# M113B.net
KiCad netlist of a schematic drawn in EAGLE
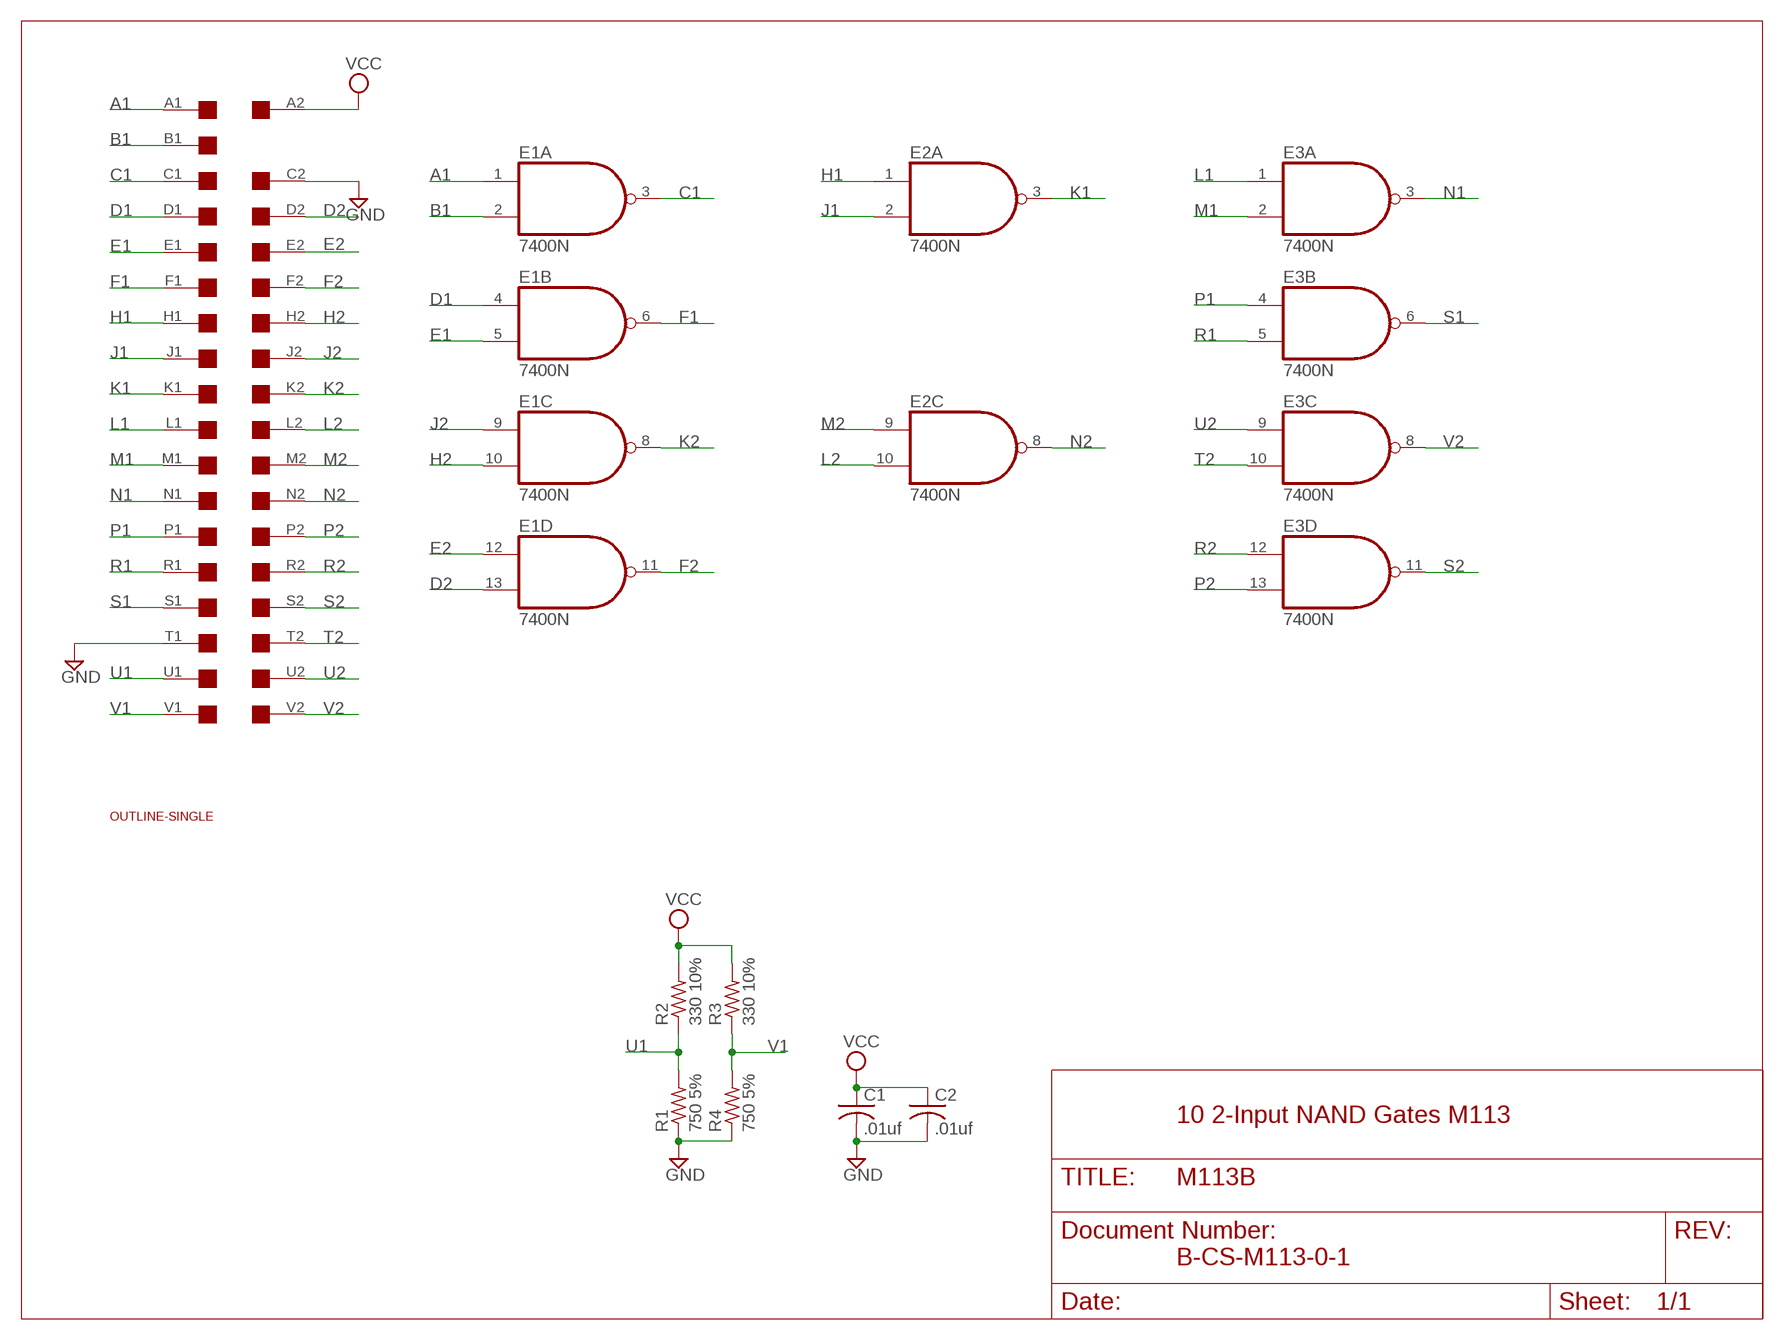
[diagram p0: schematic, sheet 1]

(export (version "E")
  (design (tool "Eeschema 10.0.6"))
  (components
    (comp (ref "C1")
      (value ".01uf")
      (footprint "eagle-import:C075-032X103")
      (libsource (lib "eagle-import") (part "C-US075-032X103"))
    )
    (comp (ref "C2")
      (value ".01uf")
      (footprint "eagle-import:C075-032X103")
      (libsource (lib "eagle-import") (part "C-US075-032X103"))
    )
    (comp (ref "E1")
      (value "7400N")
      (footprint "eagle-import:DIL14")
      (libsource (lib "eagle-import") (part "7400N"))
    )
    (comp (ref "E2")
      (value "7400N")
      (footprint "eagle-import:DIL14")
      (libsource (lib "eagle-import") (part "7400N"))
    )
    (comp (ref "E3")
      (value "7400N")
      (footprint "eagle-import:DIL14")
      (libsource (lib "eagle-import") (part "7400N"))
    )
    (comp (ref "R1")
      (value "750 5%")
      (footprint "eagle-import:0207_15")
      (libsource (lib "eagle-import") (part "R-US_0207/15"))
    )
    (comp (ref "R2")
      (value "330 10%")
      (footprint "eagle-import:0207_15")
      (libsource (lib "eagle-import") (part "R-US_0207/15"))
    )
    (comp (ref "R3")
      (value "330 10%")
      (footprint "eagle-import:0207_15")
      (libsource (lib "eagle-import") (part "R-US_0207/15"))
    )
    (comp (ref "R4")
      (value "750 5%")
      (footprint "eagle-import:0207_15")
      (libsource (lib "eagle-import") (part "R-US_0207/15"))
    )
    (comp (ref "U$1")
      (value "SINGLE")
      (footprint "eagle-import:EDGE-CON2")
      (libsource (lib "eagle-import") (part "SINGLE"))
    )
    (comp (ref "U$4")
      (value "OUTLINE-SINGLE")
      (footprint "eagle-import:SINGLE")
      (libsource (lib "eagle-import") (part "OUTLINE-SINGLE"))
    )
  )
  (nets
    (net (code "1") (name "/A1") (class "Default")
      (node (ref "E1") (pin "1") (pinfunction "I0_1") (pintype "input"))
      (node (ref "U$1") (pin "A1") (pinfunction "1_A1") (pintype "bidirectional"))
    )
    (net (code "2") (name "/B1") (class "Default")
      (node (ref "E1") (pin "2") (pinfunction "I1_2") (pintype "input"))
      (node (ref "U$1") (pin "B1") (pinfunction "1_B1") (pintype "bidirectional"))
    )
    (net (code "3") (name "/C1") (class "Default")
      (node (ref "E1") (pin "3") (pinfunction "O_3") (pintype "output"))
      (node (ref "U$1") (pin "C1") (pinfunction "1_C1") (pintype "bidirectional"))
    )
    (net (code "4") (name "/D1") (class "Default")
      (node (ref "E1") (pin "4") (pinfunction "I0_4") (pintype "input"))
      (node (ref "U$1") (pin "D1") (pinfunction "1_D1") (pintype "bidirectional"))
    )
    (net (code "5") (name "/D2") (class "Default")
      (node (ref "E1") (pin "13") (pinfunction "I1_13") (pintype "input"))
      (node (ref "U$1") (pin "D2") (pinfunction "1_D2") (pintype "bidirectional"))
    )
    (net (code "6") (name "/E1") (class "Default")
      (node (ref "E1") (pin "5") (pinfunction "I1_5") (pintype "input"))
      (node (ref "U$1") (pin "E1") (pinfunction "1_E1") (pintype "bidirectional"))
    )
    (net (code "7") (name "/E2") (class "Default")
      (node (ref "E1") (pin "12") (pinfunction "I0_12") (pintype "input"))
      (node (ref "U$1") (pin "E2") (pinfunction "1_E2") (pintype "bidirectional"))
    )
    (net (code "8") (name "/F1") (class "Default")
      (node (ref "E1") (pin "6") (pinfunction "O_6") (pintype "output"))
      (node (ref "U$1") (pin "F1") (pinfunction "1_F1") (pintype "bidirectional"))
    )
    (net (code "9") (name "/F2") (class "Default")
      (node (ref "E1") (pin "11") (pinfunction "O_11") (pintype "output"))
      (node (ref "U$1") (pin "F2") (pinfunction "1_F2") (pintype "bidirectional"))
    )
    (net (code "10") (name "/H1") (class "Default")
      (node (ref "E2") (pin "1") (pinfunction "I0_1") (pintype "input"))
      (node (ref "U$1") (pin "H1") (pinfunction "1_H1") (pintype "bidirectional"))
    )
    (net (code "11") (name "/H2") (class "Default")
      (node (ref "E1") (pin "10") (pinfunction "I1_10") (pintype "input"))
      (node (ref "U$1") (pin "H2") (pinfunction "1_H2") (pintype "bidirectional"))
    )
    (net (code "12") (name "/J1") (class "Default")
      (node (ref "E2") (pin "2") (pinfunction "I1_2") (pintype "input"))
      (node (ref "U$1") (pin "J1") (pinfunction "1_J1") (pintype "bidirectional"))
    )
    (net (code "13") (name "/J2") (class "Default")
      (node (ref "E1") (pin "9") (pinfunction "I0_9") (pintype "input"))
      (node (ref "U$1") (pin "J2") (pinfunction "1_J2") (pintype "bidirectional"))
    )
    (net (code "14") (name "/K1") (class "Default")
      (node (ref "E2") (pin "3") (pinfunction "O_3") (pintype "output"))
      (node (ref "U$1") (pin "K1") (pinfunction "1_K1") (pintype "bidirectional"))
    )
    (net (code "15") (name "/K2") (class "Default")
      (node (ref "E1") (pin "8") (pinfunction "O_8") (pintype "output"))
      (node (ref "U$1") (pin "K2") (pinfunction "1_K2") (pintype "bidirectional"))
    )
    (net (code "16") (name "/L1") (class "Default")
      (node (ref "E3") (pin "1") (pinfunction "I0_1") (pintype "input"))
      (node (ref "U$1") (pin "L1") (pinfunction "1_L1") (pintype "bidirectional"))
    )
    (net (code "17") (name "/L2") (class "Default")
      (node (ref "E2") (pin "10") (pinfunction "I1_10") (pintype "input"))
      (node (ref "U$1") (pin "L2") (pinfunction "1_L2") (pintype "bidirectional"))
    )
    (net (code "18") (name "/M1") (class "Default")
      (node (ref "E3") (pin "2") (pinfunction "I1_2") (pintype "input"))
      (node (ref "U$1") (pin "M1") (pinfunction "1_M1") (pintype "bidirectional"))
    )
    (net (code "19") (name "/M2") (class "Default")
      (node (ref "E2") (pin "9") (pinfunction "I0_9") (pintype "input"))
      (node (ref "U$1") (pin "M2") (pinfunction "1_M2") (pintype "bidirectional"))
    )
    (net (code "20") (name "/N1") (class "Default")
      (node (ref "E3") (pin "3") (pinfunction "O_3") (pintype "output"))
      (node (ref "U$1") (pin "N1") (pinfunction "1_N1") (pintype "bidirectional"))
    )
    (net (code "21") (name "/N2") (class "Default")
      (node (ref "E2") (pin "8") (pinfunction "O_8") (pintype "output"))
      (node (ref "U$1") (pin "N2") (pinfunction "1_N2") (pintype "bidirectional"))
    )
    (net (code "22") (name "/P1") (class "Default")
      (node (ref "E3") (pin "4") (pinfunction "I0_4") (pintype "input"))
      (node (ref "U$1") (pin "P1") (pinfunction "1_P1") (pintype "bidirectional"))
    )
    (net (code "23") (name "/P2") (class "Default")
      (node (ref "E3") (pin "13") (pinfunction "I1_13") (pintype "input"))
      (node (ref "U$1") (pin "P2") (pinfunction "1_P2") (pintype "bidirectional"))
    )
    (net (code "24") (name "/R1") (class "Default")
      (node (ref "E3") (pin "5") (pinfunction "I1_5") (pintype "input"))
      (node (ref "U$1") (pin "R1") (pinfunction "1_R1") (pintype "bidirectional"))
    )
    (net (code "25") (name "/R2") (class "Default")
      (node (ref "E3") (pin "12") (pinfunction "I0_12") (pintype "input"))
      (node (ref "U$1") (pin "R2") (pinfunction "1_R2") (pintype "bidirectional"))
    )
    (net (code "26") (name "/S1") (class "Default")
      (node (ref "E3") (pin "6") (pinfunction "O_6") (pintype "output"))
      (node (ref "U$1") (pin "S1") (pinfunction "1_S1") (pintype "bidirectional"))
    )
    (net (code "27") (name "/S2") (class "Default")
      (node (ref "E3") (pin "11") (pinfunction "O_11") (pintype "output"))
      (node (ref "U$1") (pin "S2") (pinfunction "1_S2") (pintype "bidirectional"))
    )
    (net (code "28") (name "/T2") (class "Default")
      (node (ref "E3") (pin "10") (pinfunction "I1_10") (pintype "input"))
      (node (ref "U$1") (pin "T2") (pinfunction "1_T2") (pintype "bidirectional"))
    )
    (net (code "29") (name "/U1") (class "Default")
      (node (ref "R1") (pin "2") (pinfunction "2_2") (pintype "passive"))
      (node (ref "R2") (pin "1") (pinfunction "1_1") (pintype "passive"))
      (node (ref "U$1") (pin "U1") (pinfunction "1_U1") (pintype "bidirectional"))
    )
    (net (code "30") (name "/U2") (class "Default")
      (node (ref "E3") (pin "9") (pinfunction "I0_9") (pintype "input"))
      (node (ref "U$1") (pin "U2") (pinfunction "1_U2") (pintype "bidirectional"))
    )
    (net (code "31") (name "/V1") (class "Default")
      (node (ref "R3") (pin "1") (pinfunction "1_1") (pintype "passive"))
      (node (ref "R4") (pin "2") (pinfunction "2_2") (pintype "passive"))
      (node (ref "U$1") (pin "V1") (pinfunction "1_V1") (pintype "bidirectional"))
    )
    (net (code "32") (name "/V2") (class "Default")
      (node (ref "E3") (pin "8") (pinfunction "O_8") (pintype "output"))
      (node (ref "U$1") (pin "V2") (pinfunction "1_V2") (pintype "bidirectional"))
    )
    (net (code "33") (name "GND") (class "Default")
      (node (ref "C1") (pin "2") (pinfunction "2_2") (pintype "passive"))
      (node (ref "C2") (pin "2") (pinfunction "2_2") (pintype "passive"))
      (node (ref "R1") (pin "1") (pinfunction "1_1") (pintype "passive"))
      (node (ref "R4") (pin "1") (pinfunction "1_1") (pintype "passive"))
      (node (ref "U$1") (pin "C2") (pinfunction "1_C2") (pintype "bidirectional"))
      (node (ref "U$1") (pin "T1") (pinfunction "1_T1") (pintype "bidirectional"))
    )
    (net (code "34") (name "VCC") (class "Default")
      (node (ref "C1") (pin "1") (pinfunction "1_1") (pintype "passive"))
      (node (ref "C2") (pin "1") (pinfunction "1_1") (pintype "passive"))
      (node (ref "R2") (pin "2") (pinfunction "2_2") (pintype "passive"))
      (node (ref "R3") (pin "2") (pinfunction "2_2") (pintype "passive"))
      (node (ref "U$1") (pin "A2") (pinfunction "1_A2") (pintype "bidirectional"))
    )
  )
)
